# EEC_Capstone-Top_Board.net
KiCad netlist of a schematic drawn in EasyEDA
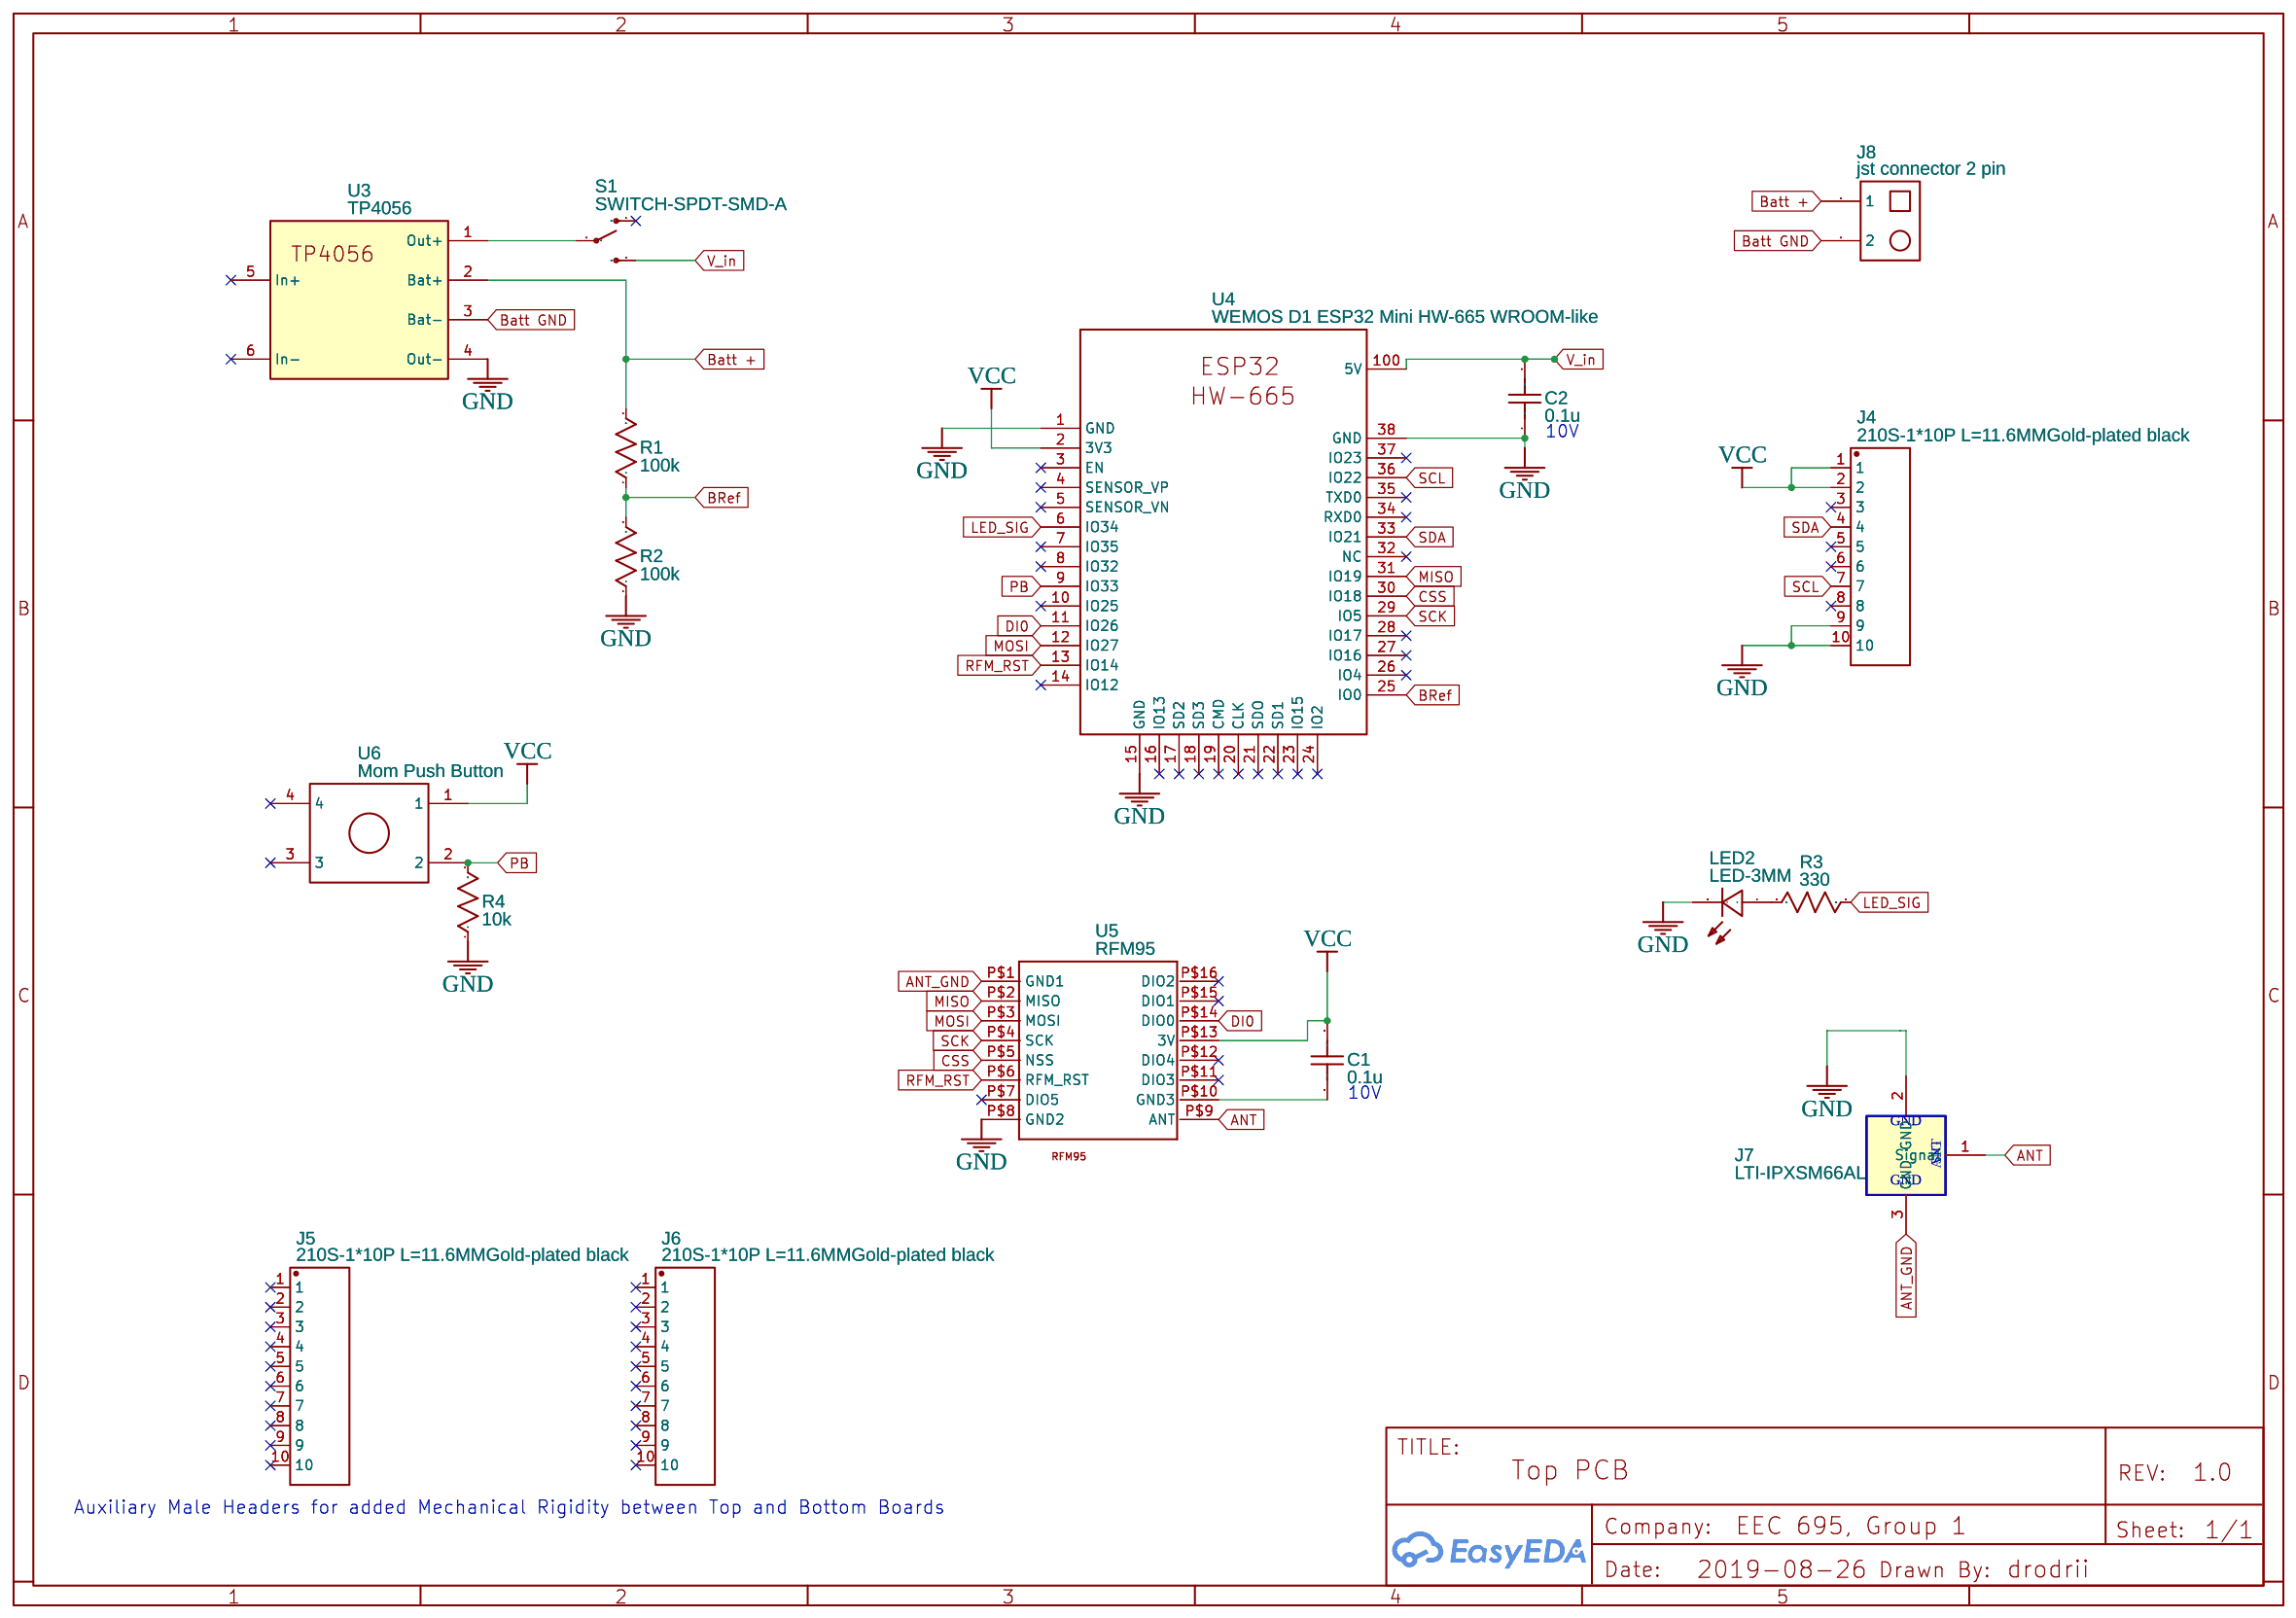
[diagram p0: schematic sheet]

(export (version "E")
  (design (tool "Eeschema 10.0.6"))
  (components
    (comp (ref "C1") (value "0.1u") (libsource (lib "") (part "Cap_0805_US")))
    (comp (ref "C2") (value "0.1u") (libsource (lib "") (part "Cap_0805_US")))
    (comp (ref "J4")
      (value "210S-1*10P L=11.6MMGold-plated black")
      (fields (field (name "BOM_Supplier Part") "C124372"))
      (libsource (lib "") (part "Unknown_940_275"))
    )
    (comp (ref "J5")
      (value "210S-1*10P L=11.6MMGold-plated black")
      (fields (field (name "BOM_Supplier Part") "C124372"))
      (libsource (lib "") (part "Unknown_150_690"))
    )
    (comp (ref "J6")
      (value "210S-1*10P L=11.6MMGold-plated black")
      (fields (field (name "BOM_Supplier Part") "C124372"))
      (libsource (lib "") (part "Unknown_335_690"))
    )
    (comp (ref "J7") (value "LTI-IPXSM66AL") (libsource (lib "") (part "Unknown_958_578")))
    (comp (ref "J8")
      (value "jst connector 2 pin")
      (fields (field (name "BOM_Manufacturer Part") "JST_XH CONNECTOR"))
      (libsource (lib "") (part "Unknown_945_105"))
    )
    (comp (ref "LED2")
      (value "LED-3MM")
      (fields
        (field (name "BOM_Manufacturer Part") "204-10SURD/S530-A3")
        (field (name "BOM_Supplier Part") "C99772")
      )
      (libsource (lib "") (part "Unknown_870_455"))
    )
    (comp (ref "R1")
      (value "100k")
      (fields (field (name "BOM_Manufacturer Part") "?"))
      (libsource (lib "") (part "Res_0805(1/8W)_US"))
    )
    (comp (ref "R2")
      (value "100k")
      (fields (field (name "BOM_Manufacturer Part") "?"))
      (libsource (lib "") (part "Res_0805(1/8W)_US"))
    )
    (comp (ref "R3")
      (value "330")
      (fields (field (name "BOM_Manufacturer Part") "?"))
      (libsource (lib "") (part "Res_0805(1/8W)_US_1"))
    )
    (comp (ref "R4")
      (value "10k")
      (fields (field (name "BOM_Manufacturer Part") "?"))
      (libsource (lib "") (part "Res_0805(1/8W)_US"))
    )
    (comp (ref "S1")
      (value "SWITCH-SPDT-SMD-A")
      (fields (field (name "BOM_Manufacturer Part") "?"))
      (libsource (lib "") (part "Unknown_300_115"))
    )
    (comp (ref "U3") (value "TP4056") (libsource (lib "") (part "Unknown_130_185")))
    (comp (ref "U4")
      (value "WEMOS D1 ESP32 Mini HW-665 WROOM-like")
      (fields (field (name "BOM_Supplier Part") "WEMOS_D1_ESP32"))
      (libsource (lib "") (part "Unknown_540_350"))
    )
    (comp (ref "U5") (value "RFM95") (libsource (lib "") (part "Unknown_550_535")))
    (comp (ref "U6")
      (value "Mom Push Button")
      (fields (field (name "BOM_Manufacturer Part") "Momentary Push Button"))
      (libsource (lib "") (part "Unknown_210_390"))
    )
  )
  (nets
    (net (code "1") (name "ANT") (class "Default")
      (node (ref "J7") (pin "1") (pinfunction "Signal_1") (pintype "input"))
      (node (ref "U5") (pin "P$9") (pinfunction "ANT_P$9") (pintype "bidirectional"))
    )
    (net (code "2") (name "ANT_GND") (class "Default")
      (node (ref "J7") (pin "3") (pinfunction "GND_3") (pintype "unspecified"))
      (node (ref "U5") (pin "P$1") (pinfunction "GND1_P$1") (pintype "bidirectional"))
    )
    (net (code "3") (name "BRef") (class "Default")
      (node (ref "R1") (pin "1") (pinfunction "1_1") (pintype "unspecified"))
      (node (ref "R2") (pin "2") (pinfunction "2_2") (pintype "unspecified"))
      (node (ref "U4") (pin "25") (pinfunction "IO0_25") (pintype "bidirectional"))
    )
    (net (code "4") (name "Batt +") (class "Default")
      (node (ref "J8") (pin "1") (pinfunction "1_1") (pintype "unspecified"))
      (node (ref "R1") (pin "2") (pinfunction "2_2") (pintype "unspecified"))
      (node (ref "U3") (pin "2") (pinfunction "Bat+_2") (pintype "unspecified"))
    )
    (net (code "5") (name "Batt GND") (class "Default")
      (node (ref "J8") (pin "2") (pinfunction "2_2") (pintype "unspecified"))
      (node (ref "U3") (pin "3") (pinfunction "Bat-_3") (pintype "unspecified"))
    )
    (net (code "6") (name "CSS") (class "Default")
      (node (ref "U4") (pin "30") (pinfunction "IO18_30") (pintype "input"))
      (node (ref "U5") (pin "P$5") (pinfunction "NSS_P$5") (pintype "bidirectional"))
    )
    (net (code "7") (name "DI0") (class "Default")
      (node (ref "U4") (pin "11") (pinfunction "IO26_11") (pintype "bidirectional"))
      (node (ref "U5") (pin "P$14") (pinfunction "DIO0_P$14") (pintype "bidirectional"))
    )
    (net (code "8") (name "GND") (class "Default")
      (node (ref "C2") (pin "1") (pinfunction "1_1") (pintype "unspecified"))
      (node (ref "J4") (pin "10") (pinfunction "10_10") (pintype "unspecified"))
      (node (ref "J4") (pin "9") (pinfunction "9_9") (pintype "unspecified"))
      (node (ref "J7") (pin "2") (pinfunction "GND_2") (pintype "unspecified"))
      (node (ref "LED2") (pin "2") (pinfunction "-_2") (pintype "unspecified"))
      (node (ref "R2") (pin "1") (pinfunction "1_1") (pintype "unspecified"))
      (node (ref "R4") (pin "1") (pinfunction "1_1") (pintype "unspecified"))
      (node (ref "U3") (pin "4") (pinfunction "Out-_4") (pintype "unspecified"))
      (node (ref "U4") (pin "1") (pinfunction "GND_1") (pintype "bidirectional"))
      (node (ref "U4") (pin "15") (pinfunction "GND_15") (pintype "bidirectional"))
      (node (ref "U4") (pin "38") (pinfunction "GND_38") (pintype "bidirectional"))
      (node (ref "U5") (pin "P$8") (pinfunction "GND2_P$8") (pintype "bidirectional"))
    )
    (net (code "9") (name "LED_SIG") (class "Default")
      (node (ref "R3") (pin "2") (pinfunction "2_2") (pintype "unspecified"))
      (node (ref "U4") (pin "6") (pinfunction "IO34_6") (pintype "bidirectional"))
    )
    (net (code "10") (name "MISO") (class "Default")
      (node (ref "U4") (pin "31") (pinfunction "IO19_31") (pintype "bidirectional"))
      (node (ref "U5") (pin "P$2") (pinfunction "MISO_P$2") (pintype "bidirectional"))
    )
    (net (code "11") (name "MOSI") (class "Default")
      (node (ref "U4") (pin "12") (pinfunction "IO27_12") (pintype "bidirectional"))
      (node (ref "U5") (pin "P$3") (pinfunction "MOSI_P$3") (pintype "bidirectional"))
    )
    (net (code "12") (name "Net-(LED2-+)") (class "Default")
      (node (ref "LED2") (pin "1") (pinfunction "+_1") (pintype "unspecified"))
      (node (ref "R3") (pin "1") (pinfunction "1_1") (pintype "unspecified"))
    )
    (net (code "13") (name "Net-(S1-P)") (class "Default")
      (node (ref "S1") (pin "2") (pinfunction "P_2") (pintype "unspecified"))
      (node (ref "U3") (pin "1") (pinfunction "Out+_1") (pintype "unspecified"))
    )
    (net (code "14") (name "Net-(U5-GND3)") (class "Default")
      (node (ref "C1") (pin "1") (pinfunction "1_1") (pintype "unspecified"))
      (node (ref "U5") (pin "P$10") (pinfunction "GND3_P$10") (pintype "bidirectional"))
    )
    (net (code "15") (name "PB") (class "Default")
      (node (ref "R4") (pin "2") (pinfunction "2_2") (pintype "unspecified"))
      (node (ref "U4") (pin "9") (pinfunction "IO33_9") (pintype "bidirectional"))
      (node (ref "U6") (pin "2") (pinfunction "2_2") (pintype "unspecified"))
    )
    (net (code "16") (name "RFM_RST") (class "Default")
      (node (ref "U4") (pin "13") (pinfunction "IO14_13") (pintype "bidirectional"))
      (node (ref "U5") (pin "P$6") (pinfunction "RFM_RST_P$6") (pintype "bidirectional"))
    )
    (net (code "17") (name "SCK") (class "Default")
      (node (ref "U4") (pin "29") (pinfunction "IO5_29") (pintype "bidirectional"))
      (node (ref "U5") (pin "P$4") (pinfunction "SCK_P$4") (pintype "bidirectional"))
    )
    (net (code "18") (name "SCL") (class "Default")
      (node (ref "J4") (pin "7") (pinfunction "7_7") (pintype "unspecified"))
      (node (ref "U4") (pin "36") (pinfunction "IO22_36") (pintype "bidirectional"))
    )
    (net (code "19") (name "SDA") (class "Default")
      (node (ref "J4") (pin "4") (pinfunction "4_4") (pintype "unspecified"))
      (node (ref "U4") (pin "33") (pinfunction "IO21_33") (pintype "bidirectional"))
    )
    (net (code "20") (name "VCC") (class "Default")
      (node (ref "C1") (pin "2") (pinfunction "2_2") (pintype "unspecified"))
      (node (ref "J4") (pin "1") (pinfunction "1_1") (pintype "unspecified"))
      (node (ref "J4") (pin "2") (pinfunction "2_2") (pintype "unspecified"))
      (node (ref "U4") (pin "2") (pinfunction "3V3_2") (pintype "bidirectional"))
      (node (ref "U5") (pin "P$13") (pinfunction "3V_P$13") (pintype "bidirectional"))
      (node (ref "U6") (pin "1") (pinfunction "1_1") (pintype "unspecified"))
    )
    (net (code "21") (name "V_in") (class "Default")
      (node (ref "C2") (pin "2") (pinfunction "2_2") (pintype "unspecified"))
      (node (ref "S1") (pin "3") (pinfunction "S_3") (pintype "unspecified"))
      (node (ref "U4") (pin "100") (pinfunction "5V_100") (pintype "bidirectional"))
    )
    (net (code "22") (name "unconnected-(J4-Pad3)") (class "Default")
      (node (ref "J4") (pin "3") (pinfunction "3_3") (pintype "unspecified+no_connect"))
    )
    (net (code "23") (name "unconnected-(J4-Pad5)") (class "Default")
      (node (ref "J4") (pin "5") (pinfunction "5_5") (pintype "unspecified+no_connect"))
    )
    (net (code "24") (name "unconnected-(J4-Pad6)") (class "Default")
      (node (ref "J4") (pin "6") (pinfunction "6_6") (pintype "unspecified+no_connect"))
    )
    (net (code "25") (name "unconnected-(J4-Pad8)") (class "Default")
      (node (ref "J4") (pin "8") (pinfunction "8_8") (pintype "unspecified+no_connect"))
    )
    (net (code "26") (name "unconnected-(J5-Pad1)") (class "Default")
      (node (ref "J5") (pin "1") (pinfunction "1_1") (pintype "unspecified+no_connect"))
    )
    (net (code "27") (name "unconnected-(J5-Pad2)") (class "Default")
      (node (ref "J5") (pin "2") (pinfunction "2_2") (pintype "unspecified+no_connect"))
    )
    (net (code "28") (name "unconnected-(J5-Pad3)") (class "Default")
      (node (ref "J5") (pin "3") (pinfunction "3_3") (pintype "unspecified+no_connect"))
    )
    (net (code "29") (name "unconnected-(J5-Pad4)") (class "Default")
      (node (ref "J5") (pin "4") (pinfunction "4_4") (pintype "unspecified+no_connect"))
    )
    (net (code "30") (name "unconnected-(J5-Pad5)") (class "Default")
      (node (ref "J5") (pin "5") (pinfunction "5_5") (pintype "unspecified+no_connect"))
    )
    (net (code "31") (name "unconnected-(J5-Pad6)") (class "Default")
      (node (ref "J5") (pin "6") (pinfunction "6_6") (pintype "unspecified+no_connect"))
    )
    (net (code "32") (name "unconnected-(J5-Pad7)") (class "Default")
      (node (ref "J5") (pin "7") (pinfunction "7_7") (pintype "unspecified+no_connect"))
    )
    (net (code "33") (name "unconnected-(J5-Pad8)") (class "Default")
      (node (ref "J5") (pin "8") (pinfunction "8_8") (pintype "unspecified+no_connect"))
    )
    (net (code "34") (name "unconnected-(J5-Pad9)") (class "Default")
      (node (ref "J5") (pin "9") (pinfunction "9_9") (pintype "unspecified+no_connect"))
    )
    (net (code "35") (name "unconnected-(J5-Pad10)") (class "Default")
      (node (ref "J5") (pin "10") (pinfunction "10_10") (pintype "unspecified+no_connect"))
    )
    (net (code "36") (name "unconnected-(J6-Pad1)") (class "Default")
      (node (ref "J6") (pin "1") (pinfunction "1_1") (pintype "unspecified+no_connect"))
    )
    (net (code "37") (name "unconnected-(J6-Pad2)") (class "Default")
      (node (ref "J6") (pin "2") (pinfunction "2_2") (pintype "unspecified+no_connect"))
    )
    (net (code "38") (name "unconnected-(J6-Pad3)") (class "Default")
      (node (ref "J6") (pin "3") (pinfunction "3_3") (pintype "unspecified+no_connect"))
    )
    (net (code "39") (name "unconnected-(J6-Pad4)") (class "Default")
      (node (ref "J6") (pin "4") (pinfunction "4_4") (pintype "unspecified+no_connect"))
    )
    (net (code "40") (name "unconnected-(J6-Pad5)") (class "Default")
      (node (ref "J6") (pin "5") (pinfunction "5_5") (pintype "unspecified+no_connect"))
    )
    (net (code "41") (name "unconnected-(J6-Pad6)") (class "Default")
      (node (ref "J6") (pin "6") (pinfunction "6_6") (pintype "unspecified+no_connect"))
    )
    (net (code "42") (name "unconnected-(J6-Pad7)") (class "Default")
      (node (ref "J6") (pin "7") (pinfunction "7_7") (pintype "unspecified+no_connect"))
    )
    (net (code "43") (name "unconnected-(J6-Pad8)") (class "Default")
      (node (ref "J6") (pin "8") (pinfunction "8_8") (pintype "unspecified+no_connect"))
    )
    (net (code "44") (name "unconnected-(J6-Pad9)") (class "Default")
      (node (ref "J6") (pin "9") (pinfunction "9_9") (pintype "unspecified+no_connect"))
    )
    (net (code "45") (name "unconnected-(J6-Pad10)") (class "Default")
      (node (ref "J6") (pin "10") (pinfunction "10_10") (pintype "unspecified+no_connect"))
    )
    (net (code "46") (name "unconnected-(S1-O-Pad1)") (class "Default")
      (node (ref "S1") (pin "1") (pinfunction "O_1") (pintype "unspecified+no_connect"))
    )
    (net (code "47") (name "unconnected-(U3-In+-Pad5)") (class "Default")
      (node (ref "U3") (pin "5") (pinfunction "In+_5") (pintype "unspecified+no_connect"))
    )
    (net (code "48") (name "unconnected-(U3-In--Pad6)") (class "Default")
      (node (ref "U3") (pin "6") (pinfunction "In-_6") (pintype "unspecified+no_connect"))
    )
    (net (code "49") (name "unconnected-(U4-CLK-Pad20)") (class "Default")
      (node (ref "U4") (pin "20") (pinfunction "CLK_20") (pintype "input+no_connect"))
    )
    (net (code "50") (name "unconnected-(U4-CMD-Pad19)") (class "Default")
      (node (ref "U4") (pin "19") (pinfunction "CMD_19") (pintype "bidirectional+no_connect"))
    )
    (net (code "51") (name "unconnected-(U4-EN-Pad3)") (class "Default")
      (node (ref "U4") (pin "3") (pinfunction "EN_3") (pintype "input+no_connect"))
    )
    (net (code "52") (name "unconnected-(U4-IO2-Pad24)") (class "Default")
      (node (ref "U4") (pin "24") (pinfunction "IO2_24") (pintype "bidirectional+no_connect"))
    )
    (net (code "53") (name "unconnected-(U4-IO4-Pad26)") (class "Default")
      (node (ref "U4") (pin "26") (pinfunction "IO4_26") (pintype "input+no_connect"))
    )
    (net (code "54") (name "unconnected-(U4-IO12-Pad14)") (class "Default")
      (node (ref "U4") (pin "14") (pinfunction "IO12_14") (pintype "bidirectional+no_connect"))
    )
    (net (code "55") (name "unconnected-(U4-IO13-Pad16)") (class "Default")
      (node (ref "U4") (pin "16") (pinfunction "IO13_16") (pintype "bidirectional+no_connect"))
    )
    (net (code "56") (name "unconnected-(U4-IO15-Pad23)") (class "Default")
      (node (ref "U4") (pin "23") (pinfunction "IO15_23") (pintype "bidirectional+no_connect"))
    )
    (net (code "57") (name "unconnected-(U4-IO16-Pad27)") (class "Default")
      (node (ref "U4") (pin "27") (pinfunction "IO16_27") (pintype "bidirectional+no_connect"))
    )
    (net (code "58") (name "unconnected-(U4-IO17-Pad28)") (class "Default")
      (node (ref "U4") (pin "28") (pinfunction "IO17_28") (pintype "bidirectional+no_connect"))
    )
    (net (code "59") (name "unconnected-(U4-IO23-Pad37)") (class "Default")
      (node (ref "U4") (pin "37") (pinfunction "IO23_37") (pintype "bidirectional+no_connect"))
    )
    (net (code "60") (name "unconnected-(U4-IO25-Pad10)") (class "Default")
      (node (ref "U4") (pin "10") (pinfunction "IO25_10") (pintype "bidirectional+no_connect"))
    )
    (net (code "61") (name "unconnected-(U4-IO32-Pad8)") (class "Default")
      (node (ref "U4") (pin "8") (pinfunction "IO32_8") (pintype "bidirectional+no_connect"))
    )
    (net (code "62") (name "unconnected-(U4-IO35-Pad7)") (class "Default")
      (node (ref "U4") (pin "7") (pinfunction "IO35_7") (pintype "bidirectional+no_connect"))
    )
    (net (code "63") (name "unconnected-(U4-NC-Pad32)") (class "Default")
      (node (ref "U4") (pin "32") (pinfunction "NC_32") (pintype "bidirectional+no_connect"))
    )
    (net (code "64") (name "unconnected-(U4-RXD0-Pad34)") (class "Default")
      (node (ref "U4") (pin "34") (pinfunction "RXD0_34") (pintype "bidirectional+no_connect"))
    )
    (net (code "65") (name "unconnected-(U4-SD1-Pad22)") (class "Default")
      (node (ref "U4") (pin "22") (pinfunction "SD1_22") (pintype "bidirectional+no_connect"))
    )
    (net (code "66") (name "unconnected-(U4-SD2-Pad17)") (class "Default")
      (node (ref "U4") (pin "17") (pinfunction "SD2_17") (pintype "bidirectional+no_connect"))
    )
    (net (code "67") (name "unconnected-(U4-SD3-Pad18)") (class "Default")
      (node (ref "U4") (pin "18") (pinfunction "SD3_18") (pintype "bidirectional+no_connect"))
    )
    (net (code "68") (name "unconnected-(U4-SDO-Pad21)") (class "Default")
      (node (ref "U4") (pin "21") (pinfunction "SDO_21") (pintype "bidirectional+no_connect"))
    )
    (net (code "69") (name "unconnected-(U4-SENSOR_VN-Pad5)") (class "Default")
      (node (ref "U4") (pin "5") (pinfunction "SENSOR_VN_5") (pintype "input+no_connect"))
    )
    (net (code "70") (name "unconnected-(U4-SENSOR_VP-Pad4)") (class "Default")
      (node (ref "U4") (pin "4") (pinfunction "SENSOR_VP_4") (pintype "input+no_connect"))
    )
    (net (code "71") (name "unconnected-(U4-TXD0-Pad35)") (class "Default")
      (node (ref "U4") (pin "35") (pinfunction "TXD0_35") (pintype "bidirectional+no_connect"))
    )
    (net (code "72") (name "unconnected-(U5-DIO1-PadP$15)") (class "Default")
      (node (ref "U5") (pin "P$15") (pinfunction "DIO1_P$15") (pintype "bidirectional+no_connect"))
    )
    (net (code "73") (name "unconnected-(U5-DIO2-PadP$16)") (class "Default")
      (node (ref "U5") (pin "P$16") (pinfunction "DIO2_P$16") (pintype "bidirectional+no_connect"))
    )
    (net (code "74") (name "unconnected-(U5-DIO3-PadP$11)") (class "Default")
      (node (ref "U5") (pin "P$11") (pinfunction "DIO3_P$11") (pintype "bidirectional+no_connect"))
    )
    (net (code "75") (name "unconnected-(U5-DIO4-PadP$12)") (class "Default")
      (node (ref "U5") (pin "P$12") (pinfunction "DIO4_P$12") (pintype "bidirectional+no_connect"))
    )
    (net (code "76") (name "unconnected-(U5-DIO5-PadP$7)") (class "Default")
      (node (ref "U5") (pin "P$7") (pinfunction "DIO5_P$7") (pintype "bidirectional+no_connect"))
    )
    (net (code "77") (name "unconnected-(U6-Pad3)") (class "Default")
      (node (ref "U6") (pin "3") (pinfunction "3_3") (pintype "unspecified+no_connect"))
    )
    (net (code "78") (name "unconnected-(U6-Pad4)") (class "Default")
      (node (ref "U6") (pin "4") (pinfunction "4_4") (pintype "unspecified+no_connect"))
    )
  )
)
